# LilyPad-E-Sewing-Kit_v15.net
KiCad netlist of a schematic drawn in EAGLE
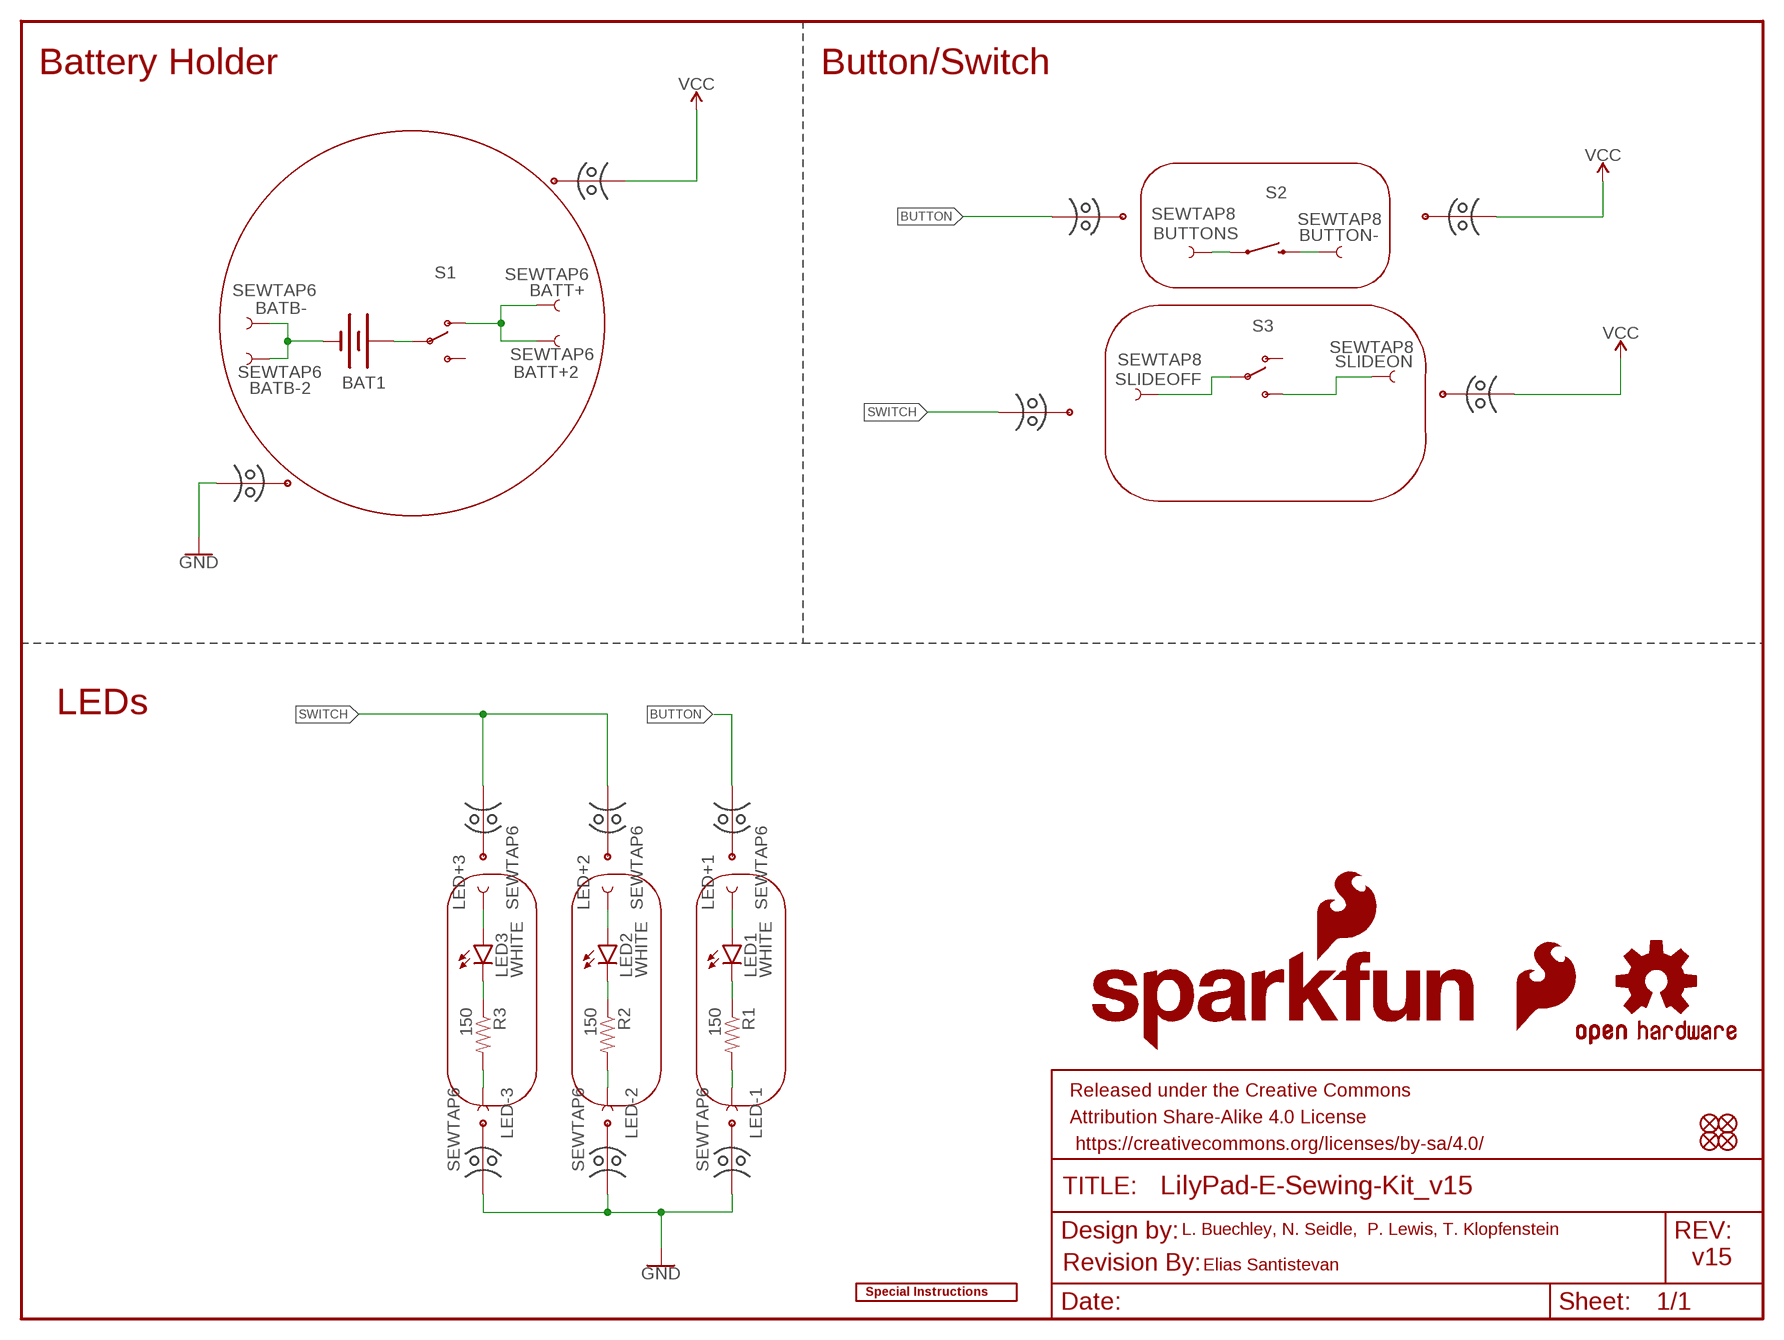
[diagram p0: schematic, sheet 1]

(export (version "E")
  (design (tool "Eeschema 10.0.6"))
  (components
    (comp (ref "BAT1")
      (value "20mm coincell")
      (footprint "eagle-import:BATTCON_20MM_4LEGS")
      (libsource (lib "eagle-import") (part "BATTERY20MM_4LEGS"))
    )
    (comp (ref "BATB-")
      (value "SEWTAP6")
      (footprint "eagle-import:PETAL-SMALL-2SIDE")
      (libsource (lib "eagle-import") (part "SEWTAP6"))
    )
    (comp (ref "BATB-2")
      (value "SEWTAP6")
      (footprint "eagle-import:PETAL-SMALL-2SIDE")
      (libsource (lib "eagle-import") (part "SEWTAP6"))
    )
    (comp (ref "BATT+")
      (value "SEWTAP6")
      (footprint "eagle-import:PETAL-SMALL-2SIDE")
      (libsource (lib "eagle-import") (part "SEWTAP6"))
    )
    (comp (ref "BATT+2")
      (value "SEWTAP6")
      (footprint "eagle-import:PETAL-SMALL-2SIDE")
      (libsource (lib "eagle-import") (part "SEWTAP6"))
    )
    (comp (ref "BUTTON-")
      (value "SEWTAP8")
      (footprint "eagle-import:PETAL-MEDIUM-2SIDE")
      (libsource (lib "eagle-import") (part "SEWTAP8"))
    )
    (comp (ref "BUTTONS")
      (value "SEWTAP8")
      (footprint "eagle-import:PETAL-MEDIUM-2SIDE")
      (libsource (lib "eagle-import") (part "SEWTAP8"))
    )
    (comp (ref "FD1")
      (value "FIDUCIALUFIDUCIAL")
      (footprint "eagle-import:MICRO-FIDUCIAL")
      (libsource (lib "eagle-import") (part "FIDUCIALUFIDUCIAL"))
    )
    (comp (ref "FD2")
      (value "FIDUCIALUFIDUCIAL")
      (footprint "eagle-import:MICRO-FIDUCIAL")
      (libsource (lib "eagle-import") (part "FIDUCIALUFIDUCIAL"))
    )
    (comp (ref "FD3")
      (value "FIDUCIALUFIDUCIAL")
      (footprint "eagle-import:MICRO-FIDUCIAL")
      (libsource (lib "eagle-import") (part "FIDUCIALUFIDUCIAL"))
    )
    (comp (ref "FD4")
      (value "FIDUCIALUFIDUCIAL")
      (footprint "eagle-import:MICRO-FIDUCIAL")
      (libsource (lib "eagle-import") (part "FIDUCIALUFIDUCIAL"))
    )
    (comp (ref "FRAME1")
      (value "FRAME-LETTER")
      (footprint "eagle-import:CREATIVE_COMMONS")
      (libsource (lib "eagle-import") (part "FRAME-LETTER"))
    )
    (comp (ref "LED+1")
      (value "SEWTAP6")
      (footprint "eagle-import:PETAL-SMALL-2SIDE")
      (libsource (lib "eagle-import") (part "SEWTAP6"))
    )
    (comp (ref "LED+2")
      (value "SEWTAP6")
      (footprint "eagle-import:PETAL-SMALL-2SIDE")
      (libsource (lib "eagle-import") (part "SEWTAP6"))
    )
    (comp (ref "LED+3")
      (value "SEWTAP6")
      (footprint "eagle-import:PETAL-SMALL-2SIDE")
      (libsource (lib "eagle-import") (part "SEWTAP6"))
    )
    (comp (ref "LED-1")
      (value "SEWTAP6")
      (footprint "eagle-import:PETAL-SMALL-2SIDE")
      (libsource (lib "eagle-import") (part "SEWTAP6"))
    )
    (comp (ref "LED-2")
      (value "SEWTAP6")
      (footprint "eagle-import:PETAL-SMALL-2SIDE")
      (libsource (lib "eagle-import") (part "SEWTAP6"))
    )
    (comp (ref "LED-3")
      (value "SEWTAP6")
      (footprint "eagle-import:PETAL-SMALL-2SIDE")
      (libsource (lib "eagle-import") (part "SEWTAP6"))
    )
    (comp (ref "LED1")
      (value "WHITE")
      (footprint "eagle-import:LED-1206")
      (libsource (lib "eagle-import") (part "LED-WHITE1206"))
    )
    (comp (ref "LED2")
      (value "WHITE")
      (footprint "eagle-import:LED-1206")
      (libsource (lib "eagle-import") (part "LED-WHITE1206"))
    )
    (comp (ref "LED3")
      (value "WHITE")
      (footprint "eagle-import:LED-1206")
      (libsource (lib "eagle-import") (part "LED-WHITE1206"))
    )
    (comp (ref "LOGO1")
      (value "SFE_LOGO_FLAME.1_INCH")
      (footprint "eagle-import:SFE_LOGO_FLAME_.1")
      (libsource (lib "eagle-import") (part "SFE_LOGO_FLAME.1_INCH"))
    )
    (comp (ref "LOGO2")
      (value "OSHW-LOGOS")
      (footprint "eagle-import:OSHW-LOGO-S")
      (libsource (lib "eagle-import") (part "OSHW-LOGOS"))
    )
    (comp (ref "LOGO3")
      (value "SFE_LOGO_NAME_FLAME.1_INCH")
      (footprint "eagle-import:SFE_LOGO_NAME_FLAME_.1")
      (libsource (lib "eagle-import") (part "SFE_LOGO_NAME_FLAME.1_INCH"))
    )
    (comp (ref "MB+")
      (value "MOUSE-BITE-12_HOLES")
      (footprint "eagle-import:MOUST-BITE-1-(2_HOLES)")
      (libsource (lib "eagle-import") (part "MOUSE-BITE-12_HOLES"))
    )
    (comp (ref "MB-")
      (value "MOUSE-BITE-12_HOLES")
      (footprint "eagle-import:MOUST-BITE-1-(2_HOLES)")
      (libsource (lib "eagle-import") (part "MOUSE-BITE-12_HOLES"))
    )
    (comp (ref "MB1")
      (value "MOUSE-BITE-12_HOLES")
      (footprint "eagle-import:MOUST-BITE-1-(2_HOLES)")
      (libsource (lib "eagle-import") (part "MOUSE-BITE-12_HOLES"))
    )
    (comp (ref "MB2")
      (value "MOUSE-BITE-12_HOLES")
      (footprint "eagle-import:MOUST-BITE-1-(2_HOLES)")
      (libsource (lib "eagle-import") (part "MOUSE-BITE-12_HOLES"))
    )
    (comp (ref "MB3")
      (value "MOUSE-BITE-12_HOLES")
      (footprint "eagle-import:MOUST-BITE-1-(2_HOLES)")
      (libsource (lib "eagle-import") (part "MOUSE-BITE-12_HOLES"))
    )
    (comp (ref "MB4")
      (value "MOUSE-BITE-12_HOLES")
      (footprint "eagle-import:MOUST-BITE-1-(2_HOLES)")
      (libsource (lib "eagle-import") (part "MOUSE-BITE-12_HOLES"))
    )
    (comp (ref "MB5")
      (value "MOUSE-BITE-12_HOLES")
      (footprint "eagle-import:MOUST-BITE-1-(2_HOLES)")
      (libsource (lib "eagle-import") (part "MOUSE-BITE-12_HOLES"))
    )
    (comp (ref "MB6")
      (value "MOUSE-BITE-12_HOLES")
      (footprint "eagle-import:MOUST-BITE-1-(2_HOLES)")
      (libsource (lib "eagle-import") (part "MOUSE-BITE-12_HOLES"))
    )
    (comp (ref "MB7")
      (value "MOUSE-BITE-12_HOLES")
      (footprint "eagle-import:MOUST-BITE-1-(2_HOLES)")
      (libsource (lib "eagle-import") (part "MOUSE-BITE-12_HOLES"))
    )
    (comp (ref "MB8")
      (value "MOUSE-BITE-12_HOLES")
      (footprint "eagle-import:MOUST-BITE-1-(2_HOLES)")
      (libsource (lib "eagle-import") (part "MOUSE-BITE-12_HOLES"))
    )
    (comp (ref "MB9")
      (value "MOUSE-BITE-12_HOLES")
      (footprint "eagle-import:MOUST-BITE-1-(2_HOLES)")
      (libsource (lib "eagle-import") (part "MOUSE-BITE-12_HOLES"))
    )
    (comp (ref "MB10")
      (value "MOUSE-BITE-12_HOLES")
      (footprint "eagle-import:MOUST-BITE-1-(2_HOLES)")
      (libsource (lib "eagle-import") (part "MOUSE-BITE-12_HOLES"))
    )
    (comp (ref "R1")
      (value "150")
      (footprint "eagle-import:0603-RES")
      (libsource (lib "eagle-import") (part "150OHM-1/10W-1%(0603)"))
    )
    (comp (ref "R2")
      (value "150")
      (footprint "eagle-import:0603-RES")
      (libsource (lib "eagle-import") (part "150OHM-1/10W-1%(0603)"))
    )
    (comp (ref "R3")
      (value "150")
      (footprint "eagle-import:0603-RES")
      (libsource (lib "eagle-import") (part "150OHM-1/10W-1%(0603)"))
    )
    (comp (ref "S1")
      (value "S1")
      (footprint "eagle-import:AYZ0202")
      (libsource (lib "eagle-import") (part "SWITCH-SPDTSMD"))
    )
    (comp (ref "S2")
      (value "SWITCH-MOMENTARY-2SMD")
      (footprint "eagle-import:TACTILE-SWITCH-SMD")
      (libsource (lib "eagle-import") (part "SWITCH-MOMENTARY-2SMD"))
    )
    (comp (ref "S3")
      (value "S3")
      (footprint "eagle-import:AYZ0202")
      (libsource (lib "eagle-import") (part "SWITCH-SPDTSMD"))
    )
    (comp (ref "SLIDEOFF")
      (value "SEWTAP8")
      (footprint "eagle-import:PETAL-MEDIUM-2SIDE")
      (libsource (lib "eagle-import") (part "SEWTAP8"))
    )
    (comp (ref "SLIDEON")
      (value "SEWTAP8")
      (footprint "eagle-import:PETAL-MEDIUM-2SIDE")
      (libsource (lib "eagle-import") (part "SEWTAP8"))
    )
    (comp (ref "U$1")
      (value "REVISION")
      (footprint "eagle-import:REVISION")
      (libsource (lib "eagle-import") (part "REVISION"))
    )
    (comp (ref "U$9")
      (value "SPECIAL_INSTRUCTIONS-ORDERING")
      (footprint "eagle-import:ORDERING_INSTRUCTIONS")
      (libsource (lib "eagle-import") (part "SPECIAL_INSTRUCTIONS-ORDERING"))
    )
  )
  (nets
    (net (code "1") (name "BUTTON") (class "Default")
      (node (ref "BUTTONS") (pin "1") (pinfunction "1_1") (pintype "bidirectional"))
      (node (ref "LED+1") (pin "1") (pinfunction "1_1") (pintype "bidirectional"))
      (node (ref "LED1") (pin "A") (pinfunction "A_A") (pintype "passive"))
      (node (ref "MB3") (pin "P$1") (pinfunction "P$1_P$1") (pintype "bidirectional"))
      (node (ref "MB9") (pin "P$1") (pinfunction "P$1_P$1") (pintype "bidirectional"))
      (node (ref "S2") (pin "1") (pinfunction "1_1") (pintype "passive"))
    )
    (net (code "2") (name "GND") (class "Default")
      (node (ref "BAT1") (pin "NEGATIVE") (pinfunction "-_NEGATIVE") (pintype "power_in"))
      (node (ref "BATB-") (pin "1") (pinfunction "1_1") (pintype "bidirectional"))
      (node (ref "BATB-2") (pin "1") (pinfunction "1_1") (pintype "bidirectional"))
      (node (ref "LED-1") (pin "1") (pinfunction "1_1") (pintype "bidirectional"))
      (node (ref "LED-2") (pin "1") (pinfunction "1_1") (pintype "bidirectional"))
      (node (ref "LED-3") (pin "1") (pinfunction "1_1") (pintype "bidirectional"))
      (node (ref "MB-") (pin "P$1") (pinfunction "P$1_P$1") (pintype "bidirectional"))
      (node (ref "MB6") (pin "P$1") (pinfunction "P$1_P$1") (pintype "bidirectional"))
      (node (ref "MB7") (pin "P$1") (pinfunction "P$1_P$1") (pintype "bidirectional"))
      (node (ref "MB8") (pin "P$1") (pinfunction "P$1_P$1") (pintype "bidirectional"))
      (node (ref "R1") (pin "2") (pinfunction "2_2") (pintype "passive"))
      (node (ref "R2") (pin "2") (pinfunction "2_2") (pintype "passive"))
      (node (ref "R3") (pin "2") (pinfunction "2_2") (pintype "passive"))
    )
    (net (code "3") (name "Net-(LED1-PadC)") (class "Default")
      (node (ref "LED1") (pin "C") (pinfunction "C_C") (pintype "passive"))
      (node (ref "R1") (pin "1") (pinfunction "1_1") (pintype "passive"))
    )
    (net (code "4") (name "Net-(LED2-PadC)") (class "Default")
      (node (ref "LED2") (pin "C") (pinfunction "C_C") (pintype "passive"))
      (node (ref "R2") (pin "1") (pinfunction "1_1") (pintype "passive"))
    )
    (net (code "5") (name "Net-(LED3-PadC)") (class "Default")
      (node (ref "LED3") (pin "C") (pinfunction "C_C") (pintype "passive"))
      (node (ref "R3") (pin "1") (pinfunction "1_1") (pintype "passive"))
    )
    (net (code "6") (name "Net-(S1-P)") (class "Default")
      (node (ref "BAT1") (pin "POSITIVE@1") (pinfunction "+_POSITIVE@1") (pintype "power_in"))
      (node (ref "BAT1") (pin "POSITIVE@2") (pinfunction "+_POSITIVE@2") (pintype "power_in"))
      (node (ref "BAT1") (pin "POSITIVE@3") (pinfunction "+_POSITIVE@3") (pintype "power_in"))
      (node (ref "BAT1") (pin "POSITIVE@4") (pinfunction "+_POSITIVE@4") (pintype "power_in"))
      (node (ref "S1") (pin "2") (pinfunction "P_2") (pintype "passive"))
    )
    (net (code "7") (name "SWITCH") (class "Default")
      (node (ref "LED+2") (pin "1") (pinfunction "1_1") (pintype "bidirectional"))
      (node (ref "LED+3") (pin "1") (pinfunction "1_1") (pintype "bidirectional"))
      (node (ref "LED2") (pin "A") (pinfunction "A_A") (pintype "passive"))
      (node (ref "LED3") (pin "A") (pinfunction "A_A") (pintype "passive"))
      (node (ref "MB10") (pin "P$1") (pinfunction "P$1_P$1") (pintype "bidirectional"))
      (node (ref "MB4") (pin "P$1") (pinfunction "P$1_P$1") (pintype "bidirectional"))
      (node (ref "MB5") (pin "P$1") (pinfunction "P$1_P$1") (pintype "bidirectional"))
      (node (ref "S3") (pin "2") (pinfunction "P_2") (pintype "passive"))
      (node (ref "SLIDEOFF") (pin "1") (pinfunction "1_1") (pintype "bidirectional"))
    )
    (net (code "8") (name "VCC") (class "Default")
      (node (ref "BATT+") (pin "1") (pinfunction "1_1") (pintype "bidirectional"))
      (node (ref "BATT+2") (pin "1") (pinfunction "1_1") (pintype "bidirectional"))
      (node (ref "BUTTON-") (pin "1") (pinfunction "1_1") (pintype "bidirectional"))
      (node (ref "MB+") (pin "P$1") (pinfunction "P$1_P$1") (pintype "bidirectional"))
      (node (ref "MB1") (pin "P$1") (pinfunction "P$1_P$1") (pintype "bidirectional"))
      (node (ref "MB2") (pin "P$1") (pinfunction "P$1_P$1") (pintype "bidirectional"))
      (node (ref "S1") (pin "1") (pinfunction "O_1") (pintype "passive"))
      (node (ref "S2") (pin "3") (pinfunction "2_3") (pintype "passive"))
      (node (ref "S3") (pin "3") (pinfunction "S_3") (pintype "passive"))
      (node (ref "SLIDEON") (pin "1") (pinfunction "1_1") (pintype "bidirectional"))
    )
    (net (code "9") (name "unconnected-(S1-S-Pad3)") (class "Default")
      (node (ref "S1") (pin "3") (pinfunction "S_3") (pintype "passive"))
    )
    (net (code "10") (name "unconnected-(S3-O-Pad1)") (class "Default")
      (node (ref "S3") (pin "1") (pinfunction "O_1") (pintype "passive"))
    )
  )
)
